# SB_Valve_3_v1_1.net
KiCad netlist of a schematic drawn in Altium Designer
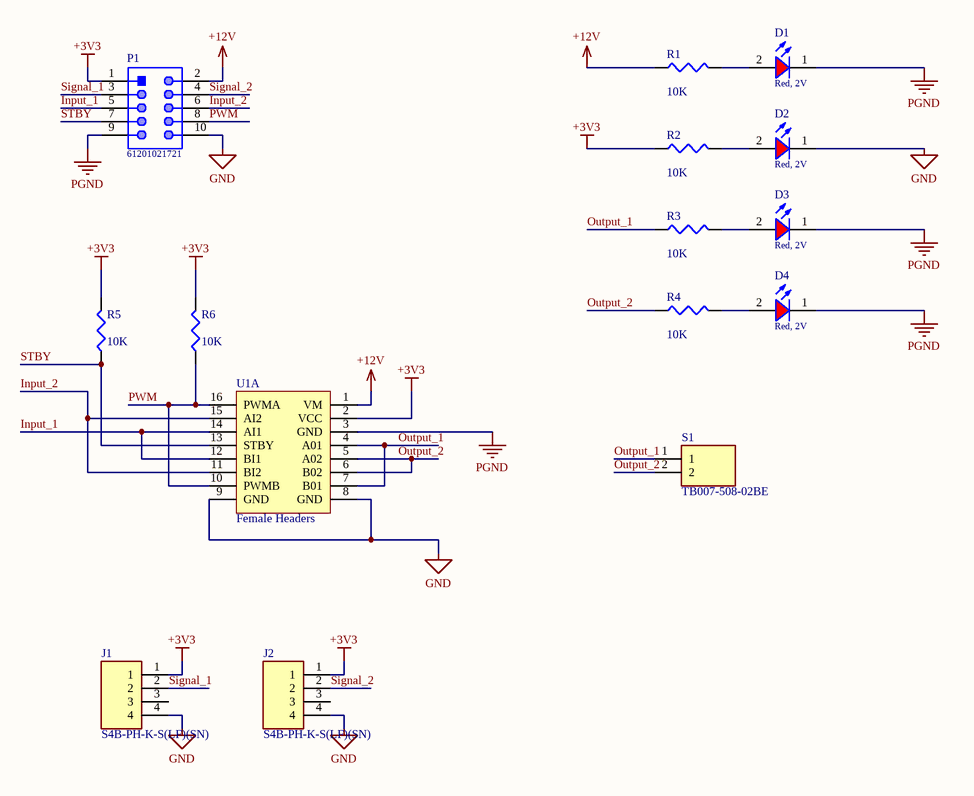
[diagram p0: SB_Valve_3_v1.1.SchDoc]

(export (version "E")
  (design (tool "Eeschema 10.0.6"))
  (components
    (comp (ref "D1")
      (value "Red, 2V")
      (footprint "WL-SMSW_0603_Rectangular")
      (description "WL-SMSW SMT Mono-color Side View Waterclear, size 0603, Red, 2V, 140deg")
      (fields
        (field (name "MANUFACTURER PART NUMBER") "155060RS75300")
        (field (name "MANUFACTURER") "Wurth Elektronik")
      )
      (libsource (lib "WL-SMSW (rev20b)") (part "155060RS75300"))
    )
    (comp (ref "D2")
      (value "Red, 2V")
      (footprint "WL-SMSW_0603_Rectangular")
      (description "WL-SMSW SMT Mono-color Side View Waterclear, size 0603, Red, 2V, 140deg")
      (fields
        (field (name "MANUFACTURER PART NUMBER") "155060RS75300")
        (field (name "MANUFACTURER") "Wurth Elektronik")
      )
      (libsource (lib "WL-SMSW (rev20b)") (part "155060RS75300"))
    )
    (comp (ref "D3")
      (value "Red, 2V")
      (footprint "WL-SMSW_0603_Rectangular")
      (description "WL-SMSW SMT Mono-color Side View Waterclear, size 0603, Red, 2V, 140deg")
      (fields
        (field (name "MANUFACTURER PART NUMBER") "155060RS75300")
        (field (name "MANUFACTURER") "Wurth Elektronik")
      )
      (libsource (lib "WL-SMSW (rev20b)") (part "155060RS75300"))
    )
    (comp (ref "D4")
      (value "Red, 2V")
      (footprint "WL-SMSW_0603_Rectangular")
      (description "WL-SMSW SMT Mono-color Side View Waterclear, size 0603, Red, 2V, 140deg")
      (fields
        (field (name "MANUFACTURER PART NUMBER") "155060RS75300")
        (field (name "MANUFACTURER") "Wurth Elektronik")
      )
      (libsource (lib "WL-SMSW (rev20b)") (part "155060RS75300"))
    )
    (comp (ref "J1")
      (value "S4B-PH-K-S(LF)(SN)")
      (footprint "JST_S4B-PH-K-S(LF)(SN)")
      (description "Connector Header Through Hole, Right Angle 4 position 0.079 _2.00mm_")
      (fields (field (name "MP") "S4B-PH-K-S_LF__SN_") (field (name "MF") "JST Sales"))
      (libsource (lib "S4B-PH-K-S_LF__SN_") (part "S4B-PH-K-S(LF)(SN)"))
    )
    (comp (ref "J2")
      (value "S4B-PH-K-S(LF)(SN)")
      (footprint "JST_S4B-PH-K-S(LF)(SN)")
      (description "Connector Header Through Hole, Right Angle 4 position 0.079 _2.00mm_")
      (fields (field (name "MP") "S4B-PH-K-S_LF__SN_") (field (name "MF") "JST Sales"))
      (libsource (lib "S4B-PH-K-S_LF__SN_") (part "S4B-PH-K-S(LF)(SN)"))
    )
    (comp (ref "P1")
      (value "61201021721")
      (footprint "61201021721")
      (description "Male Box Header WR-BHD, THT, Angled, pitch 2.54 mm, 10 pins")
      (fields (field (name "MANUFACTURER") "Wurth Elektronik") (field (name "PUBLISHER") "WurthElektronik"))
      (libsource (lib "Altium Content Vault") (part "WE-CN-2P-M-R10"))
    )
    (comp (ref "R1")
      (value "10K")
      (footprint "J1-0603")
      (description "Resistor")
      (fields (field (name "Comment") "R4") (field (name "PUBLISHER") "Altium Limited"))
      (libsource (lib "Miscellaneous Devices") (part "Res3"))
    )
    (comp (ref "R2")
      (value "10K")
      (footprint "J1-0603")
      (description "Resistor")
      (fields (field (name "Comment") "R3") (field (name "PUBLISHER") "Altium Limited"))
      (libsource (lib "Miscellaneous Devices") (part "Res3"))
    )
    (comp (ref "R3")
      (value "10K")
      (footprint "J1-0603")
      (description "Resistor")
      (fields (field (name "Comment") "R5") (field (name "PUBLISHER") "Altium Limited"))
      (libsource (lib "Miscellaneous Devices") (part "Res3"))
    )
    (comp (ref "R4")
      (value "10K")
      (footprint "J1-0603")
      (description "Resistor")
      (fields (field (name "Comment") "R6") (field (name "PUBLISHER") "Altium Limited"))
      (libsource (lib "Miscellaneous Devices") (part "Res3"))
    )
    (comp (ref "R5")
      (value "10K")
      (footprint "J1-0603")
      (description "Resistor")
      (fields (field (name "Comment") "R2") (field (name "PUBLISHER") "Altium Limited"))
      (libsource (lib "Miscellaneous Devices") (part "Res3"))
    )
    (comp (ref "R6")
      (value "10K")
      (footprint "J1-0603")
      (description "Resistor")
      (fields (field (name "Comment") "R1") (field (name "PUBLISHER") "Altium Limited"))
      (libsource (lib "Miscellaneous Devices") (part "Res3"))
    )
    (comp (ref "S1")
      (value "TB007-508-02BE")
      (footprint "CUI_TB007-508-02BE")
      (description "2~24 Poles, Screw Type, Horizontal, 5.08 Pitch, 24~12 _AWG_, Terminal Block Connector")
      (fields (field (name "MF") "CUI Devices"))
      (libsource (lib "TB007-508-02BE") (part "TB007-508-02BE"))
    )
    (comp (ref "U1")
      (value "Female Headers")
      (footprint "TB6612FNG")
      (description "Motor Driver")
      (libsource (lib "SectionE_BreakOut") (part "TB6612FNG Female"))
    )
  )
  (nets
    (net (code "1") (name "+3V3") (class "Default")
      (node (ref "J1") (pin "1") (pinfunction "1_1") (pintype "passive"))
      (node (ref "J2") (pin "1") (pinfunction "1_1") (pintype "passive"))
      (node (ref "P1") (pin "1") (pinfunction "1_1") (pintype "passive"))
      (node (ref "R2") (pin "1") (pinfunction "1_1") (pintype "passive"))
      (node (ref "R5") (pin "2") (pinfunction "2_2") (pintype "passive"))
      (node (ref "R6") (pin "2") (pinfunction "2_2") (pintype "passive"))
      (node (ref "U1") (pin "2") (pinfunction "VCC_2") (pintype "passive"))
    )
    (net (code "2") (name "+12V") (class "Default")
      (node (ref "P1") (pin "2") (pinfunction "2_2") (pintype "passive"))
      (node (ref "R1") (pin "1") (pinfunction "1_1") (pintype "passive"))
      (node (ref "U1") (pin "1") (pinfunction "VM_1") (pintype "passive"))
    )
    (net (code "3") (name "/Input_1") (class "Default")
      (node (ref "P1") (pin "5") (pinfunction "5_5") (pintype "passive"))
      (node (ref "U1") (pin "12") (pinfunction "BI1_12") (pintype "passive"))
      (node (ref "U1") (pin "14") (pinfunction "AI1_14") (pintype "passive"))
    )
    (net (code "4") (name "/Input_2") (class "Default")
      (node (ref "P1") (pin "6") (pinfunction "6_6") (pintype "passive"))
      (node (ref "U1") (pin "11") (pinfunction "BI2_11") (pintype "passive"))
      (node (ref "U1") (pin "15") (pinfunction "AI2_15") (pintype "passive"))
    )
    (net (code "5") (name "/Output_1") (class "Default")
      (node (ref "R3") (pin "1") (pinfunction "1_1") (pintype "passive"))
      (node (ref "S1") (pin "1") (pinfunction "1_1") (pintype "passive"))
      (node (ref "U1") (pin "4") (pinfunction "A01_4") (pintype "passive"))
      (node (ref "U1") (pin "7") (pinfunction "B01_7") (pintype "passive"))
    )
    (net (code "6") (name "/Output_2") (class "Default")
      (node (ref "R4") (pin "1") (pinfunction "1_1") (pintype "passive"))
      (node (ref "S1") (pin "2") (pinfunction "2_2") (pintype "passive"))
      (node (ref "U1") (pin "5") (pinfunction "A02_5") (pintype "passive"))
      (node (ref "U1") (pin "6") (pinfunction "B02_6") (pintype "passive"))
    )
    (net (code "7") (name "/PWM") (class "Default")
      (node (ref "P1") (pin "8") (pinfunction "8_8") (pintype "passive"))
      (node (ref "R6") (pin "1") (pinfunction "1_1") (pintype "passive"))
      (node (ref "U1") (pin "10") (pinfunction "PWMB_10") (pintype "passive"))
      (node (ref "U1") (pin "16") (pinfunction "PWMA_16") (pintype "passive"))
    )
    (net (code "8") (name "/STBY") (class "Default")
      (node (ref "P1") (pin "7") (pinfunction "7_7") (pintype "passive"))
      (node (ref "R5") (pin "1") (pinfunction "1_1") (pintype "passive"))
      (node (ref "U1") (pin "13") (pinfunction "STBY_13") (pintype "passive"))
    )
    (net (code "9") (name "/Signal_1") (class "Default")
      (node (ref "J1") (pin "2") (pinfunction "2_2") (pintype "passive"))
      (node (ref "P1") (pin "3") (pinfunction "3_3") (pintype "passive"))
    )
    (net (code "10") (name "/Signal_2") (class "Default")
      (node (ref "J2") (pin "2") (pinfunction "2_2") (pintype "passive"))
      (node (ref "P1") (pin "4") (pinfunction "4_4") (pintype "passive"))
    )
    (net (code "11") (name "GND") (class "Default")
      (node (ref "D2") (pin "1") (pinfunction "K_1") (pintype "passive"))
      (node (ref "J1") (pin "4") (pinfunction "4_4") (pintype "passive"))
      (node (ref "J2") (pin "4") (pinfunction "4_4") (pintype "passive"))
      (node (ref "P1") (pin "10") (pinfunction "10_10") (pintype "passive"))
      (node (ref "U1") (pin "8") (pinfunction "GND_8") (pintype "passive"))
      (node (ref "U1") (pin "9") (pinfunction "GND_9") (pintype "passive"))
    )
    (net (code "12") (name "Net-(D1-A)") (class "Default")
      (node (ref "D1") (pin "2") (pinfunction "A_2") (pintype "passive"))
      (node (ref "R1") (pin "2") (pinfunction "2_2") (pintype "passive"))
    )
    (net (code "13") (name "Net-(D2-A)") (class "Default")
      (node (ref "D2") (pin "2") (pinfunction "A_2") (pintype "passive"))
      (node (ref "R2") (pin "2") (pinfunction "2_2") (pintype "passive"))
    )
    (net (code "14") (name "Net-(D3-A)") (class "Default")
      (node (ref "D3") (pin "2") (pinfunction "A_2") (pintype "passive"))
      (node (ref "R3") (pin "2") (pinfunction "2_2") (pintype "passive"))
    )
    (net (code "15") (name "Net-(D4-A)") (class "Default")
      (node (ref "D4") (pin "2") (pinfunction "A_2") (pintype "passive"))
      (node (ref "R4") (pin "2") (pinfunction "2_2") (pintype "passive"))
    )
    (net (code "16") (name "PGND") (class "Default")
      (node (ref "D1") (pin "1") (pinfunction "K_1") (pintype "passive"))
      (node (ref "D3") (pin "1") (pinfunction "K_1") (pintype "passive"))
      (node (ref "D4") (pin "1") (pinfunction "K_1") (pintype "passive"))
      (node (ref "P1") (pin "9") (pinfunction "9_9") (pintype "passive"))
      (node (ref "U1") (pin "3") (pinfunction "GND_3") (pintype "passive"))
    )
    (net (code "17") (name "unconnected-(J1-Pad3)") (class "Default")
      (node (ref "J1") (pin "3") (pinfunction "3_3") (pintype "passive"))
    )
    (net (code "18") (name "unconnected-(J2-Pad3)") (class "Default")
      (node (ref "J2") (pin "3") (pinfunction "3_3") (pintype "passive"))
    )
  )
)
